# schematic_slave_5_air_pressure.net
KiCad netlist of a schematic drawn in EAGLE
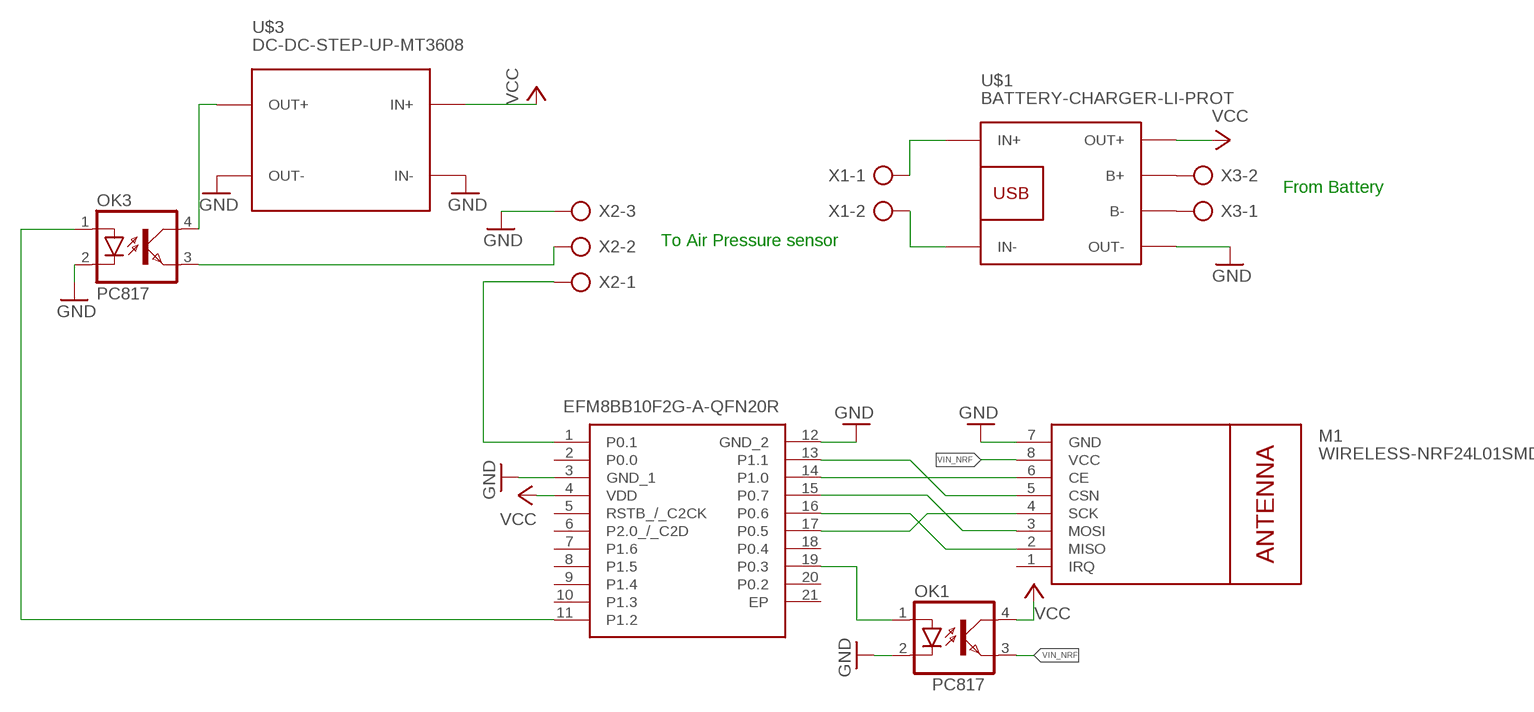
[diagram p0: schematic, sheet 1]

(export (version "E")
  (design (tool "Eeschema 10.0.6"))
  (components
    (comp (ref "IC1")
      (value "EFM8BB10F2G-A-QFN20R")
      (footprint "eagle-import:EFM8BB10F2GAQFN20R")
      (fields (field (name "MOUSER_PART_NUMBER") "634-8BB10F2GAQF20R"))
      (libsource (lib "eagle-import") (part "EFM8BB10F2G-A-QFN20R"))
    )
    (comp (ref "M1")
      (value "WIRELESS-NRF24L01SMD")
      (footprint "eagle-import:WIRELESS-NRF24L01-SMD")
      (libsource (lib "eagle-import") (part "WIRELESS-NRF24L01SMD"))
    )
    (comp (ref "OK1")
      (value "PC817")
      (footprint "eagle-import:DIL04")
      (fields (field (name "MPN") "PC817X4J000F"))
      (libsource (lib "eagle-import") (part "PC817"))
    )
    (comp (ref "OK3")
      (value "PC817")
      (footprint "eagle-import:DIL04")
      (fields (field (name "MPN") "PC817X4J000F"))
      (libsource (lib "eagle-import") (part "PC817"))
    )
    (comp (ref "U$1")
      (value "BATTERY-CHARGER-LI-PROT")
      (footprint "eagle-import:BATTERY-CHARGER-LI-PROT")
      (libsource (lib "eagle-import") (part "BATTERY-CHARGER-LI-PROT"))
    )
    (comp (ref "U$3")
      (value "DC-DC-STEP-UP-MT3608")
      (footprint "eagle-import:DC-DC-STEP-UP-MT3608")
      (libsource (lib "eagle-import") (part "DC-DC-STEP-UP-MT3608"))
    )
    (comp (ref "X1")
      (value "AK500/2-H")
      (footprint "eagle-import:AK500_2-H")
      (libsource (lib "eagle-import") (part "AK500/2-H"))
    )
    (comp (ref "X2")
      (value "AK500/3-H")
      (footprint "eagle-import:AK500_3-H")
      (libsource (lib "eagle-import") (part "AK500/3-H"))
    )
    (comp (ref "X3")
      (value "AK500/2-H")
      (footprint "eagle-import:AK500_2-H")
      (libsource (lib "eagle-import") (part "AK500/2-H"))
    )
  )
  (nets
    (net (code "1") (name "GND") (class "Default")
      (node (ref "IC1") (pin "12") (pinfunction "GND_2_12") (pintype "bidirectional"))
      (node (ref "IC1") (pin "3") (pinfunction "GND_1_3") (pintype "bidirectional"))
      (node (ref "M1") (pin "7") (pinfunction "GND_7") (pintype "power_in"))
      (node (ref "OK1") (pin "2") (pinfunction "C_2") (pintype "passive"))
      (node (ref "OK3") (pin "2") (pinfunction "C_2") (pintype "passive"))
      (node (ref "U$1") (pin "OUT-") (pinfunction "OUT-_OUT-") (pintype "bidirectional"))
      (node (ref "U$3") (pin "IN-") (pinfunction "IN-_IN-") (pintype "bidirectional"))
      (node (ref "U$3") (pin "OUT-") (pinfunction "OUT-_OUT-") (pintype "bidirectional"))
      (node (ref "X2") (pin "3") (pinfunction "KL_3") (pintype "passive"))
    )
    (net (code "2") (name "Net-(IC1-P0.1)") (class "Default")
      (node (ref "IC1") (pin "1") (pinfunction "P0.1_1") (pintype "bidirectional"))
      (node (ref "X2") (pin "1") (pinfunction "KL_1") (pintype "passive"))
    )
    (net (code "3") (name "Net-(IC1-P0.3)") (class "Default")
      (node (ref "IC1") (pin "19") (pinfunction "P0.3_19") (pintype "bidirectional"))
      (node (ref "OK1") (pin "1") (pinfunction "A_1") (pintype "passive"))
    )
    (net (code "4") (name "Net-(IC1-P0.5)") (class "Default")
      (node (ref "IC1") (pin "17") (pinfunction "P0.5_17") (pintype "bidirectional"))
      (node (ref "M1") (pin "4") (pinfunction "SCK_4") (pintype "bidirectional"))
    )
    (net (code "5") (name "Net-(IC1-P0.6)") (class "Default")
      (node (ref "IC1") (pin "16") (pinfunction "P0.6_16") (pintype "bidirectional"))
      (node (ref "M1") (pin "2") (pinfunction "MISO_2") (pintype "bidirectional"))
    )
    (net (code "6") (name "Net-(IC1-P0.7)") (class "Default")
      (node (ref "IC1") (pin "15") (pinfunction "P0.7_15") (pintype "bidirectional"))
      (node (ref "M1") (pin "3") (pinfunction "MOSI_3") (pintype "bidirectional"))
    )
    (net (code "7") (name "Net-(IC1-P1.0)") (class "Default")
      (node (ref "IC1") (pin "14") (pinfunction "P1.0_14") (pintype "bidirectional"))
      (node (ref "M1") (pin "6") (pinfunction "CE_6") (pintype "bidirectional"))
    )
    (net (code "8") (name "Net-(IC1-P1.1)") (class "Default")
      (node (ref "IC1") (pin "13") (pinfunction "P1.1_13") (pintype "bidirectional"))
      (node (ref "M1") (pin "5") (pinfunction "CSN_5") (pintype "bidirectional"))
    )
    (net (code "9") (name "Net-(IC1-P1.2)") (class "Default")
      (node (ref "IC1") (pin "11") (pinfunction "P1.2_11") (pintype "bidirectional"))
      (node (ref "OK3") (pin "1") (pinfunction "A_1") (pintype "passive"))
    )
    (net (code "10") (name "Net-(OK3-COL)") (class "Default")
      (node (ref "OK3") (pin "4") (pinfunction "COL_4") (pintype "passive"))
      (node (ref "U$3") (pin "OUT+") (pinfunction "OUT+_OUT+") (pintype "bidirectional"))
    )
    (net (code "11") (name "Net-(OK3-EMIT)") (class "Default")
      (node (ref "OK3") (pin "3") (pinfunction "EMIT_3") (pintype "passive"))
      (node (ref "X2") (pin "2") (pinfunction "KL_2") (pintype "passive"))
    )
    (net (code "12") (name "Net-(X1A-KL)") (class "Default")
      (node (ref "U$1") (pin "IN+") (pinfunction "IN+_IN+") (pintype "bidirectional"))
      (node (ref "X1") (pin "1") (pinfunction "KL_1") (pintype "passive"))
    )
    (net (code "13") (name "Net-(X1B-KL)") (class "Default")
      (node (ref "U$1") (pin "IN-") (pinfunction "IN-_IN-") (pintype "bidirectional"))
      (node (ref "X1") (pin "2") (pinfunction "KL_2") (pintype "passive"))
    )
    (net (code "14") (name "Net-(X3A-KL)") (class "Default")
      (node (ref "U$1") (pin "B-") (pinfunction "B-_B-") (pintype "bidirectional"))
      (node (ref "X3") (pin "1") (pinfunction "KL_1") (pintype "passive"))
    )
    (net (code "15") (name "Net-(X3B-KL)") (class "Default")
      (node (ref "U$1") (pin "B+") (pinfunction "B+_B+") (pintype "bidirectional"))
      (node (ref "X3") (pin "2") (pinfunction "KL_2") (pintype "passive"))
    )
    (net (code "16") (name "VCC") (class "Default")
      (node (ref "IC1") (pin "4") (pinfunction "VDD_4") (pintype "bidirectional"))
      (node (ref "OK1") (pin "4") (pinfunction "COL_4") (pintype "passive"))
      (node (ref "U$1") (pin "OUT+") (pinfunction "OUT+_OUT+") (pintype "bidirectional"))
      (node (ref "U$3") (pin "IN+") (pinfunction "IN+_IN+") (pintype "bidirectional"))
    )
    (net (code "17") (name "VIN_NRF") (class "Default")
      (node (ref "M1") (pin "8") (pinfunction "VCC_8") (pintype "power_in"))
      (node (ref "OK1") (pin "3") (pinfunction "EMIT_3") (pintype "passive"))
    )
    (net (code "18") (name "unconnected-(IC1-EP-Pad21)") (class "Default")
      (node (ref "IC1") (pin "21") (pinfunction "EP_21") (pintype "bidirectional"))
    )
    (net (code "19") (name "unconnected-(IC1-P0.0-Pad2)") (class "Default")
      (node (ref "IC1") (pin "2") (pinfunction "P0.0_2") (pintype "bidirectional"))
    )
    (net (code "20") (name "unconnected-(IC1-P0.2-Pad20)") (class "Default")
      (node (ref "IC1") (pin "20") (pinfunction "P0.2_20") (pintype "bidirectional"))
    )
    (net (code "21") (name "unconnected-(IC1-P0.4-Pad18)") (class "Default")
      (node (ref "IC1") (pin "18") (pinfunction "P0.4_18") (pintype "bidirectional"))
    )
    (net (code "22") (name "unconnected-(IC1-P1.3-Pad10)") (class "Default")
      (node (ref "IC1") (pin "10") (pinfunction "P1.3_10") (pintype "bidirectional"))
    )
    (net (code "23") (name "unconnected-(IC1-P1.4-Pad9)") (class "Default")
      (node (ref "IC1") (pin "9") (pinfunction "P1.4_9") (pintype "bidirectional"))
    )
    (net (code "24") (name "unconnected-(IC1-P1.5-Pad8)") (class "Default")
      (node (ref "IC1") (pin "8") (pinfunction "P1.5_8") (pintype "bidirectional"))
    )
    (net (code "25") (name "unconnected-(IC1-P1.6-Pad7)") (class "Default")
      (node (ref "IC1") (pin "7") (pinfunction "P1.6_7") (pintype "bidirectional"))
    )
    (net (code "26") (name "unconnected-(IC1-P2.0_{slash}_C2D-Pad6)") (class "Default")
      (node (ref "IC1") (pin "6") (pinfunction "P2.0_/_C2D_6") (pintype "bidirectional"))
    )
    (net (code "27") (name "unconnected-(IC1-RSTB_{slash}_C2CK-Pad5)") (class "Default")
      (node (ref "IC1") (pin "5") (pinfunction "RSTB_/_C2CK_5") (pintype "bidirectional"))
    )
    (net (code "28") (name "unconnected-(M1-IRQ-Pad1)") (class "Default")
      (node (ref "M1") (pin "1") (pinfunction "IRQ_1") (pintype "bidirectional"))
    )
  )
)
